# Adafruit_SMT_Datalogger_Shield_rev_C.net
KiCad netlist of a schematic drawn in EAGLE
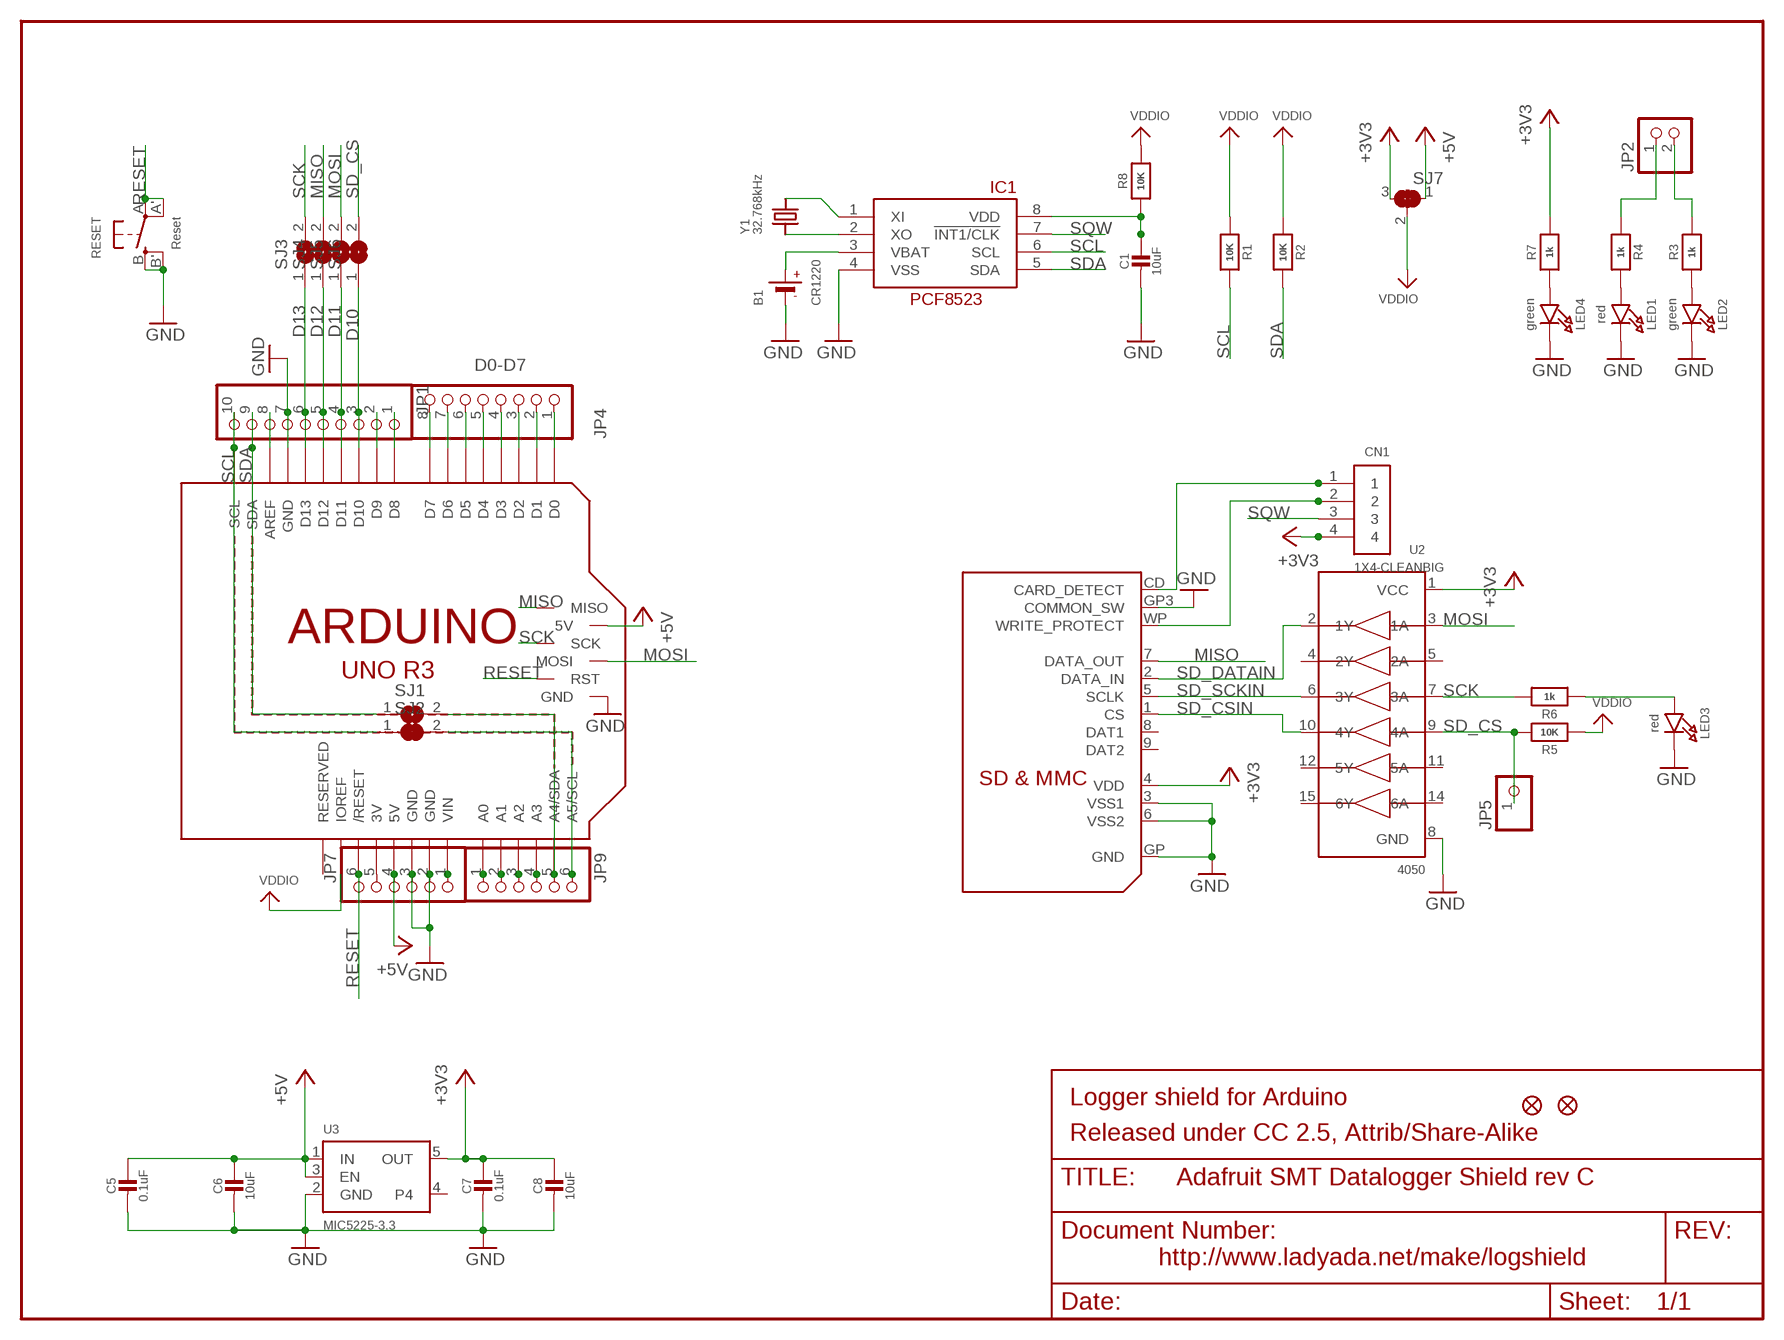
[diagram p0: schematic, sheet 1]

(export (version "E")
  (design (tool "Eeschema 10.0.6"))
  (components
    (comp (ref "B1")
      (value "CR1220")
      (footprint "eagle-import:CR1220")
      (libsource (lib "eagle-import") (part "BATTERYCR1220_SMT"))
    )
    (comp (ref "C1")
      (value "10uF")
      (footprint "eagle-import:0805-NO")
      (libsource (lib "eagle-import") (part "CAP_CERAMIC0805-NOOUTLINE"))
    )
    (comp (ref "C5")
      (value "0.1uF")
      (footprint "eagle-import:0805-NO")
      (libsource (lib "eagle-import") (part "CAP_CERAMIC0805-NOOUTLINE"))
    )
    (comp (ref "C6")
      (value "10uF")
      (footprint "eagle-import:0805-NO")
      (libsource (lib "eagle-import") (part "CAP_CERAMIC0805-NOOUTLINE"))
    )
    (comp (ref "C7")
      (value "0.1uF")
      (footprint "eagle-import:0805-NO")
      (libsource (lib "eagle-import") (part "CAP_CERAMIC0805-NOOUTLINE"))
    )
    (comp (ref "C8")
      (value "10uF")
      (footprint "eagle-import:0805-NO")
      (libsource (lib "eagle-import") (part "CAP_CERAMIC0805-NOOUTLINE"))
    )
    (comp (ref "CN1")
      (value "1X4-CLEANBIG")
      (footprint "eagle-import:1X04-CLEANBIG")
      (libsource (lib "eagle-import") (part "1X4-CLEANBIG"))
    )
    (comp (ref "FID1")
      (value "FIDUCIAL_1MM")
      (footprint "eagle-import:FIDUCIAL_1MM")
      (libsource (lib "eagle-import") (part "FIDUCIAL_1MM"))
    )
    (comp (ref "FID3")
      (value "FIDUCIAL_1MM")
      (footprint "eagle-import:FIDUCIAL_1MM")
      (libsource (lib "eagle-import") (part "FIDUCIAL_1MM"))
    )
    (comp (ref "IC1")
      (value "PCF8523T")
      (footprint "eagle-import:SOIC8_150MIL")
      (libsource (lib "eagle-import") (part "RTC_PCF8523T"))
    )
    (comp (ref "JP1")
      (value "HEADER-1X1070MIL")
      (footprint "eagle-import:1X10_ROUND70")
      (libsource (lib "eagle-import") (part "HEADER-1X1070MIL"))
    )
    (comp (ref "JP2")
      (value "HEADER-1X2ROUND")
      (footprint "eagle-import:1X02_ROUND")
      (libsource (lib "eagle-import") (part "HEADER-1X2ROUND"))
    )
    (comp (ref "JP4")
      (value "D0-D7")
      (footprint "eagle-import:1X08-BIG")
      (libsource (lib "eagle-import") (part "PINHD-1X8BIG"))
    )
    (comp (ref "JP5")
      (value "HEADER-1X1ROUND")
      (footprint "eagle-import:1X01_ROUND")
      (libsource (lib "eagle-import") (part "HEADER-1X1ROUND"))
    )
    (comp (ref "JP7")
      (value "PINHD-1X6B")
      (footprint "eagle-import:1X06-BIG")
      (libsource (lib "eagle-import") (part "PINHD-1X6B"))
    )
    (comp (ref "JP9")
      (value "PINHD-1X6B")
      (footprint "eagle-import:1X06-BIG")
      (libsource (lib "eagle-import") (part "PINHD-1X6B"))
    )
    (comp (ref "LED1")
      (value "red")
      (footprint "eagle-import:CHIPLED_0805_NOOUTLINE")
      (libsource (lib "eagle-import") (part "LED0805_NOOUTLINE"))
    )
    (comp (ref "LED2")
      (value "green")
      (footprint "eagle-import:CHIPLED_0805_NOOUTLINE")
      (libsource (lib "eagle-import") (part "LED0805_NOOUTLINE"))
    )
    (comp (ref "LED3")
      (value "red")
      (footprint "eagle-import:CHIPLED_0805_NOOUTLINE")
      (libsource (lib "eagle-import") (part "LED0805_NOOUTLINE"))
    )
    (comp (ref "LED4")
      (value "green")
      (footprint "eagle-import:CHIPLED_0805_NOOUTLINE")
      (libsource (lib "eagle-import") (part "LED0805_NOOUTLINE"))
    )
    (comp (ref "M1")
      (value "ARDUINO_R3_ICSP_NODIM")
      (footprint "eagle-import:ARDUINOR3_ICSP_NODIM")
      (libsource (lib "eagle-import") (part "ARDUINO_R3_ICSP_NODIM"))
    )
    (comp (ref "R1")
      (value "10K")
      (footprint "eagle-import:0805-NO")
      (libsource (lib "eagle-import") (part "RESISTOR0805_NOOUTLINE"))
    )
    (comp (ref "R2")
      (value "10K")
      (footprint "eagle-import:0805-NO")
      (libsource (lib "eagle-import") (part "RESISTOR0805_NOOUTLINE"))
    )
    (comp (ref "R3")
      (value "1k")
      (footprint "eagle-import:0805-NO")
      (libsource (lib "eagle-import") (part "RESISTOR0805_NOOUTLINE"))
    )
    (comp (ref "R4")
      (value "1k")
      (footprint "eagle-import:0805-NO")
      (libsource (lib "eagle-import") (part "RESISTOR0805_NOOUTLINE"))
    )
    (comp (ref "R5")
      (value "10K")
      (footprint "eagle-import:0805-NO")
      (libsource (lib "eagle-import") (part "RESISTOR0805_NOOUTLINE"))
    )
    (comp (ref "R6")
      (value "1k")
      (footprint "eagle-import:0805-NO")
      (libsource (lib "eagle-import") (part "RESISTOR0805_NOOUTLINE"))
    )
    (comp (ref "R7")
      (value "1k")
      (footprint "eagle-import:0805-NO")
      (libsource (lib "eagle-import") (part "RESISTOR0805_NOOUTLINE"))
    )
    (comp (ref "R8")
      (value "10K")
      (footprint "eagle-import:0805-NO")
      (libsource (lib "eagle-import") (part "RESISTOR0805_NOOUTLINE"))
    )
    (comp (ref "RESET")
      (value "Reset")
      (footprint "eagle-import:EVQ-Q2_SMALLER")
      (libsource (lib "eagle-import") (part "SWITCH_TACT_SMT_EVQQ2_SMALL"))
    )
    (comp (ref "SJ1")
      (value "SOLDERJUMPER")
      (footprint "eagle-import:SOLDERJUMPER_ARROW_NOPASTE")
      (libsource (lib "eagle-import") (part "SOLDERJUMPER"))
    )
    (comp (ref "SJ2")
      (value "SOLDERJUMPER")
      (footprint "eagle-import:SOLDERJUMPER_ARROW_NOPASTE")
      (libsource (lib "eagle-import") (part "SOLDERJUMPER"))
    )
    (comp (ref "SJ3")
      (value "SOLDERJUMPER")
      (footprint "eagle-import:SOLDERJUMPER_ARROW_NOPASTE")
      (libsource (lib "eagle-import") (part "SOLDERJUMPER"))
    )
    (comp (ref "SJ4")
      (value "SOLDERJUMPER")
      (footprint "eagle-import:SOLDERJUMPER_ARROW_NOPASTE")
      (libsource (lib "eagle-import") (part "SOLDERJUMPER"))
    )
    (comp (ref "SJ5")
      (value "SOLDERJUMPER")
      (footprint "eagle-import:SOLDERJUMPER_ARROW_NOPASTE")
      (libsource (lib "eagle-import") (part "SOLDERJUMPER"))
    )
    (comp (ref "SJ6")
      (value "SOLDERJUMPERCLOSED")
      (footprint "eagle-import:SOLDERJUMPER_CLOSEDWIRE")
      (libsource (lib "eagle-import") (part "SOLDERJUMPERCLOSED"))
    )
    (comp (ref "SJ7")
      (value "SOLDERJUMPER_2WAY")
      (footprint "eagle-import:SOLDERJUMPER_2WAY_OPEN_NOPASTE")
      (libsource (lib "eagle-import") (part "SOLDERJUMPER_2WAY"))
    )
    (comp (ref "U$2")
      (value "SDMMC06132")
      (footprint "eagle-import:06132")
      (libsource (lib "eagle-import") (part "SDMMC06132"))
    )
    (comp (ref "U2")
      (value "4050")
      (footprint "eagle-import:SOIC16")
      (libsource (lib "eagle-import") (part "74HC4050D"))
    )
    (comp (ref "U3")
      (value "MIC5225-3.3")
      (footprint "eagle-import:SOT23-5")
      (libsource (lib "eagle-import") (part "VREG_SOT23-5"))
    )
    (comp (ref "Y1")
      (value "32.768kHz")
      (footprint "eagle-import:CRYSTAL_8X3.8")
      (libsource (lib "eagle-import") (part "CRYSTAL8.0X3.8"))
    )
  )
  (nets
    (net (code "1") (name "+3V3") (class "Default")
      (node (ref "C7") (pin "1") (pinfunction "1_1") (pintype "passive"))
      (node (ref "C8") (pin "1") (pinfunction "1_1") (pintype "passive"))
      (node (ref "CN1") (pin "4") (pinfunction "4_4") (pintype "bidirectional"))
      (node (ref "R7") (pin "2") (pinfunction "2_2") (pintype "passive"))
      (node (ref "SJ7") (pin "3") (pinfunction "3_3") (pintype "passive"))
      (node (ref "U$2") (pin "4") (pinfunction "VDD_4") (pintype "power_in"))
      (node (ref "U2") (pin "1") (pinfunction "VCC_1") (pintype "bidirectional"))
      (node (ref "U3") (pin "5") (pinfunction "OUT_5") (pintype "power_in"))
    )
    (net (code "2") (name "+5V") (class "Default")
      (node (ref "C5") (pin "1") (pinfunction "1_1") (pintype "passive"))
      (node (ref "C6") (pin "1") (pinfunction "1_1") (pintype "passive"))
      (node (ref "JP7") (pin "4") (pinfunction "4_4") (pintype "passive"))
      (node (ref "M1") (pin "5V") (pinfunction "5V_5V") (pintype "power_in"))
      (node (ref "M1") (pin "5V_ICSP") (pinfunction "5V_5V_ICSP") (pintype "passive"))
      (node (ref "SJ7") (pin "1") (pinfunction "1_1") (pintype "passive"))
      (node (ref "U3") (pin "1") (pinfunction "IN_1") (pintype "power_in"))
      (node (ref "U3") (pin "3") (pinfunction "EN_3") (pintype "input"))
    )
    (net (code "3") (name "/D10") (class "Default")
      (node (ref "JP1") (pin "3") (pinfunction "3_3") (pintype "passive"))
      (node (ref "M1") (pin "D10") (pinfunction "D10_D10") (pintype "bidirectional"))
      (node (ref "SJ6") (pin "1") (pinfunction "1_1") (pintype "passive"))
    )
    (net (code "4") (name "/D11") (class "Default")
      (node (ref "JP1") (pin "4") (pinfunction "4_4") (pintype "passive"))
      (node (ref "M1") (pin "D11") (pinfunction "D11_D11") (pintype "bidirectional"))
      (node (ref "SJ5") (pin "1") (pinfunction "1_1") (pintype "passive"))
    )
    (net (code "5") (name "/D12") (class "Default")
      (node (ref "JP1") (pin "5") (pinfunction "5_5") (pintype "passive"))
      (node (ref "M1") (pin "D12") (pinfunction "D12_D12") (pintype "bidirectional"))
      (node (ref "SJ4") (pin "1") (pinfunction "1_1") (pintype "passive"))
    )
    (net (code "6") (name "/D13") (class "Default")
      (node (ref "JP1") (pin "6") (pinfunction "6_6") (pintype "passive"))
      (node (ref "M1") (pin "D13") (pinfunction "D13_D13") (pintype "bidirectional"))
      (node (ref "SJ3") (pin "1") (pinfunction "1_1") (pintype "passive"))
    )
    (net (code "7") (name "/MISO") (class "Default")
      (node (ref "M1") (pin "MISO") (pinfunction "MISO_MISO") (pintype "passive"))
      (node (ref "SJ4") (pin "2") (pinfunction "2_2") (pintype "passive"))
      (node (ref "U$2") (pin "7") (pinfunction "DATA_OUT_7") (pintype "output"))
    )
    (net (code "8") (name "/MOSI") (class "Default")
      (node (ref "M1") (pin "MOSI") (pinfunction "MOSI_MOSI") (pintype "passive"))
      (node (ref "SJ5") (pin "2") (pinfunction "2_2") (pintype "passive"))
      (node (ref "U2") (pin "3") (pinfunction "1A_3") (pintype "bidirectional"))
    )
    (net (code "9") (name "/RESET") (class "Default")
      (node (ref "JP7") (pin "6") (pinfunction "6_6") (pintype "passive"))
      (node (ref "M1") (pin "RESET") (pinfunction "/RESET_RESET") (pintype "bidirectional"))
      (node (ref "M1") (pin "RESET_ICSP") (pinfunction "RST_RESET_ICSP") (pintype "passive"))
      (node (ref "RESET") (pin "A") (pinfunction "P_A") (pintype "passive"))
      (node (ref "RESET") (pin "A'") (pinfunction "P1_A'") (pintype "passive"))
    )
    (net (code "10") (name "/SCK") (class "Default")
      (node (ref "M1") (pin "SCK") (pinfunction "SCK_SCK") (pintype "passive"))
      (node (ref "R6") (pin "2") (pinfunction "2_2") (pintype "passive"))
      (node (ref "SJ3") (pin "2") (pinfunction "2_2") (pintype "passive"))
      (node (ref "U2") (pin "7") (pinfunction "3A_7") (pintype "bidirectional"))
    )
    (net (code "11") (name "/SCL") (class "Default")
      (node (ref "IC1") (pin "6") (pinfunction "SCL_6") (pintype "bidirectional"))
      (node (ref "JP1") (pin "10") (pinfunction "10_10") (pintype "passive"))
      (node (ref "M1") (pin "SCL") (pinfunction "SCL_SCL") (pintype "bidirectional"))
      (node (ref "R1") (pin "2") (pinfunction "2_2") (pintype "passive"))
      (node (ref "SJ2") (pin "1") (pinfunction "1_1") (pintype "passive"))
    )
    (net (code "12") (name "/SDA") (class "Default")
      (node (ref "IC1") (pin "5") (pinfunction "SDA_5") (pintype "bidirectional"))
      (node (ref "JP1") (pin "9") (pinfunction "9_9") (pintype "passive"))
      (node (ref "M1") (pin "SDA") (pinfunction "SDA_SDA") (pintype "bidirectional"))
      (node (ref "R2") (pin "2") (pinfunction "2_2") (pintype "passive"))
      (node (ref "SJ1") (pin "1") (pinfunction "1_1") (pintype "passive"))
    )
    (net (code "13") (name "/SD_CS") (class "Default")
      (node (ref "JP5") (pin "1") (pinfunction "1_1") (pintype "passive"))
      (node (ref "R5") (pin "2") (pinfunction "2_2") (pintype "passive"))
      (node (ref "SJ6") (pin "2") (pinfunction "2_2") (pintype "passive"))
      (node (ref "U2") (pin "9") (pinfunction "4A_9") (pintype "bidirectional"))
    )
    (net (code "14") (name "/SD_CSIN") (class "Default")
      (node (ref "U$2") (pin "1") (pinfunction "CS_1") (pintype "input"))
      (node (ref "U2") (pin "10") (pinfunction "4Y_10") (pintype "bidirectional"))
    )
    (net (code "15") (name "/SD_DATAIN") (class "Default")
      (node (ref "U$2") (pin "2") (pinfunction "DATA_IN_2") (pintype "input"))
      (node (ref "U2") (pin "2") (pinfunction "1Y_2") (pintype "bidirectional"))
    )
    (net (code "16") (name "/SD_SCKIN") (class "Default")
      (node (ref "U$2") (pin "5") (pinfunction "SCLK_5") (pintype "input"))
      (node (ref "U2") (pin "6") (pinfunction "3Y_6") (pintype "bidirectional"))
    )
    (net (code "17") (name "/SQW") (class "Default")
      (node (ref "CN1") (pin "3") (pinfunction "3_3") (pintype "bidirectional"))
      (node (ref "IC1") (pin "7") (pinfunction "~{INT1/CLK}_7") (pintype "output"))
    )
    (net (code "18") (name "GND") (class "Default")
      (node (ref "B1") (pin "-") (pinfunction "-_-") (pintype "passive"))
      (node (ref "C1") (pin "2") (pinfunction "2_2") (pintype "passive"))
      (node (ref "C5") (pin "2") (pinfunction "2_2") (pintype "passive"))
      (node (ref "C6") (pin "2") (pinfunction "2_2") (pintype "passive"))
      (node (ref "C7") (pin "2") (pinfunction "2_2") (pintype "passive"))
      (node (ref "C8") (pin "2") (pinfunction "2_2") (pintype "passive"))
      (node (ref "IC1") (pin "4") (pinfunction "VSS_4") (pintype "power_in"))
      (node (ref "JP1") (pin "7") (pinfunction "7_7") (pintype "passive"))
      (node (ref "JP7") (pin "2") (pinfunction "2_2") (pintype "passive"))
      (node (ref "JP7") (pin "3") (pinfunction "3_3") (pintype "passive"))
      (node (ref "LED1") (pin "C") (pinfunction "C_C") (pintype "passive"))
      (node (ref "LED2") (pin "C") (pinfunction "C_C") (pintype "passive"))
      (node (ref "LED3") (pin "C") (pinfunction "C_C") (pintype "passive"))
      (node (ref "LED4") (pin "C") (pinfunction "C_C") (pintype "passive"))
      (node (ref "M1") (pin "GND") (pinfunction "GND_GND") (pintype "power_in"))
      (node (ref "M1") (pin "GND@1") (pinfunction "GND_GND@1") (pintype "power_in"))
      (node (ref "M1") (pin "GND@2") (pinfunction "GND_GND@2") (pintype "passive"))
      (node (ref "M1") (pin "GND@3") (pinfunction "GND_GND@3") (pintype "power_in"))
      (node (ref "RESET") (pin "B") (pinfunction "S_B") (pintype "passive"))
      (node (ref "RESET") (pin "B'") (pinfunction "S1_B'") (pintype "passive"))
      (node (ref "U$2") (pin "3") (pinfunction "VSS1_3") (pintype "power_in"))
      (node (ref "U$2") (pin "6") (pinfunction "VSS2_6") (pintype "power_in"))
      (node (ref "U$2") (pin "GP") (pinfunction "GND_GP") (pintype "power_in"))
      (node (ref "U$2") (pin "GP3") (pinfunction "COMMON_SW_GP3") (pintype "passive"))
      (node (ref "U2") (pin "8") (pinfunction "GND_8") (pintype "bidirectional"))
      (node (ref "U3") (pin "2") (pinfunction "GND_2") (pintype "power_in"))
    )
    (net (code "19") (name "Net-(IC1-VBAT)") (class "Default")
      (node (ref "B1") (pin "+$1") (pinfunction "+_+$1") (pintype "passive"))
      (node (ref "B1") (pin "+$2") (pinfunction "+_+$2") (pintype "passive"))
      (node (ref "IC1") (pin "3") (pinfunction "VBAT_3") (pintype "power_in"))
    )
    (net (code "20") (name "Net-(IC1-VDD)") (class "Default")
      (node (ref "C1") (pin "1") (pinfunction "1_1") (pintype "passive"))
      (node (ref "IC1") (pin "8") (pinfunction "VDD_8") (pintype "power_in"))
      (node (ref "R8") (pin "1") (pinfunction "1_1") (pintype "passive"))
    )
    (net (code "21") (name "Net-(IC1-XI)") (class "Default")
      (node (ref "IC1") (pin "1") (pinfunction "XI_1") (pintype "input"))
      (node (ref "Y1") (pin "P$4") (pinfunction "2_P$4") (pintype "passive"))
    )
    (net (code "22") (name "Net-(IC1-XO)") (class "Default")
      (node (ref "IC1") (pin "2") (pinfunction "XO_2") (pintype "output"))
      (node (ref "Y1") (pin "P$1") (pinfunction "1_P$1") (pintype "passive"))
    )
    (net (code "23") (name "Net-(JP1-Pad1)") (class "Default")
      (node (ref "JP1") (pin "1") (pinfunction "1_1") (pintype "passive"))
      (node (ref "M1") (pin "D8") (pinfunction "D8_D8") (pintype "bidirectional"))
    )
    (net (code "24") (name "Net-(JP1-Pad2)") (class "Default")
      (node (ref "JP1") (pin "2") (pinfunction "2_2") (pintype "passive"))
      (node (ref "M1") (pin "D9") (pinfunction "D9_D9") (pintype "bidirectional"))
    )
    (net (code "25") (name "Net-(JP1-Pad8)") (class "Default")
      (node (ref "JP1") (pin "8") (pinfunction "8_8") (pintype "passive"))
      (node (ref "M1") (pin "AREF") (pinfunction "AREF_AREF") (pintype "bidirectional"))
    )
    (net (code "26") (name "Net-(JP2-Pad1)") (class "Default")
      (node (ref "JP2") (pin "1") (pinfunction "1_1") (pintype "passive"))
      (node (ref "R4") (pin "1") (pinfunction "1_1") (pintype "passive"))
    )
    (net (code "27") (name "Net-(JP2-Pad2)") (class "Default")
      (node (ref "JP2") (pin "2") (pinfunction "2_2") (pintype "passive"))
      (node (ref "R3") (pin "2") (pinfunction "2_2") (pintype "passive"))
    )
    (net (code "28") (name "Net-(JP4-Pad1)") (class "Default")
      (node (ref "JP4") (pin "1") (pinfunction "1_1") (pintype "passive"))
      (node (ref "M1") (pin "D0") (pinfunction "D0_D0") (pintype "bidirectional"))
    )
    (net (code "29") (name "Net-(JP4-Pad2)") (class "Default")
      (node (ref "JP4") (pin "2") (pinfunction "2_2") (pintype "passive"))
      (node (ref "M1") (pin "D1") (pinfunction "D1_D1") (pintype "bidirectional"))
    )
    (net (code "30") (name "Net-(JP4-Pad3)") (class "Default")
      (node (ref "JP4") (pin "3") (pinfunction "3_3") (pintype "passive"))
      (node (ref "M1") (pin "D2") (pinfunction "D2_D2") (pintype "bidirectional"))
    )
    (net (code "31") (name "Net-(JP4-Pad4)") (class "Default")
      (node (ref "JP4") (pin "4") (pinfunction "4_4") (pintype "passive"))
      (node (ref "M1") (pin "D3") (pinfunction "D3_D3") (pintype "bidirectional"))
    )
    (net (code "32") (name "Net-(JP4-Pad5)") (class "Default")
      (node (ref "JP4") (pin "5") (pinfunction "5_5") (pintype "passive"))
      (node (ref "M1") (pin "D4") (pinfunction "D4_D4") (pintype "bidirectional"))
    )
    (net (code "33") (name "Net-(JP4-Pad6)") (class "Default")
      (node (ref "JP4") (pin "6") (pinfunction "6_6") (pintype "passive"))
      (node (ref "M1") (pin "D5") (pinfunction "D5_D5") (pintype "bidirectional"))
    )
    (net (code "34") (name "Net-(JP4-Pad7)") (class "Default")
      (node (ref "JP4") (pin "7") (pinfunction "7_7") (pintype "passive"))
      (node (ref "M1") (pin "D6") (pinfunction "D6_D6") (pintype "bidirectional"))
    )
    (net (code "35") (name "Net-(JP4-Pad8)") (class "Default")
      (node (ref "JP4") (pin "8") (pinfunction "8_8") (pintype "passive"))
      (node (ref "M1") (pin "D7") (pinfunction "D7_D7") (pintype "bidirectional"))
    )
    (net (code "36") (name "Net-(JP7-Pad1)") (class "Default")
      (node (ref "JP7") (pin "1") (pinfunction "1_1") (pintype "passive"))
      (node (ref "M1") (pin "VIN") (pinfunction "VIN_VIN") (pintype "power_in"))
    )
    (net (code "37") (name "Net-(JP7-Pad5)") (class "Default")
      (node (ref "JP7") (pin "5") (pinfunction "5_5") (pintype "passive"))
      (node (ref "M1") (pin "3V") (pinfunction "3V_3V") (pintype "power_in"))
    )
    (net (code "38") (name "Net-(JP9-Pad1)") (class "Default")
      (node (ref "JP9") (pin "1") (pinfunction "1_1") (pintype "passive"))
      (node (ref "M1") (pin "A0") (pinfunction "A0_A0") (pintype "bidirectional"))
    )
    (net (code "39") (name "Net-(JP9-Pad2)") (class "Default")
      (node (ref "JP9") (pin "2") (pinfunction "2_2") (pintype "passive"))
      (node (ref "M1") (pin "A1") (pinfunction "A1_A1") (pintype "bidirectional"))
    )
    (net (code "40") (name "Net-(JP9-Pad3)") (class "Default")
      (node (ref "JP9") (pin "3") (pinfunction "3_3") (pintype "passive"))
      (node (ref "M1") (pin "A2") (pinfunction "A2_A2") (pintype "bidirectional"))
    )
    (net (code "41") (name "Net-(JP9-Pad4)") (class "Default")
      (node (ref "JP9") (pin "4") (pinfunction "4_4") (pintype "passive"))
      (node (ref "M1") (pin "A3") (pinfunction "A3_A3") (pintype "bidirectional"))
    )
    (net (code "42") (name "Net-(LED1-PadA)") (class "Default")
      (node (ref "LED1") (pin "A") (pinfunction "A_A") (pintype "passive"))
      (node (ref "R4") (pin "2") (pinfunction "2_2") (pintype "passive"))
    )
    (net (code "43") (name "Net-(LED2-PadA)") (class "Default")
      (node (ref "LED2") (pin "A") (pinfunction "A_A") (pintype "passive"))
      (node (ref "R3") (pin "1") (pinfunction "1_1") (pintype "passive"))
    )
    (net (code "44") (name "Net-(LED3-PadA)") (class "Default")
      (node (ref "LED3") (pin "A") (pinfunction "A_A") (pintype "passive"))
      (node (ref "R6") (pin "1") (pinfunction "1_1") (pintype "passive"))
    )
    (net (code "45") (name "Net-(LED4-PadA)") (class "Default")
      (node (ref "LED4") (pin "A") (pinfunction "A_A") (pintype "passive"))
      (node (ref "R7") (pin "1") (pinfunction "1_1") (pintype "passive"))
    )
    (net (code "46") (name "Net-(M1-A4{slash}SDA)") (class "Default")
      (node (ref "JP9") (pin "5") (pinfunction "5_5") (pintype "passive"))
      (node (ref "M1") (pin "A4") (pinfunction "A4/SDA_A4") (pintype "bidirectional"))
      (node (ref "SJ1") (pin "2") (pinfunction "2_2") (pintype "passive"))
    )
    (net (code "47") (name "Net-(M1-A5{slash}SCL)") (class "Default")
      (node (ref "JP9") (pin "6") (pinfunction "6_6") (pintype "passive"))
      (node (ref "M1") (pin "A5") (pinfunction "A5/SCL_A5") (pintype "bidirectional"))
      (node (ref "SJ2") (pin "2") (pinfunction "2_2") (pintype "passive"))
    )
    (net (code "48") (name "Net-(U$2-CARD_DETECT)") (class "Default")
      (node (ref "CN1") (pin "1") (pinfunction "1_1") (pintype "bidirectional"))
      (node (ref "U$2") (pin "CD") (pinfunction "CARD_DETECT_CD") (pintype "passive"))
    )
    (net (code "49") (name "Net-(U$2-WRITE_PROTECT)") (class "Default")
      (node (ref "CN1") (pin "2") (pinfunction "2_2") (pintype "bidirectional"))
      (node (ref "U$2") (pin "WP") (pinfunction "WRITE_PROTECT_WP") (pintype "passive"))
    )
    (net (code "50") (name "VDDIO") (class "Default")
      (node (ref "M1") (pin "IOREF") (pinfunction "IOREF_IOREF") (pintype "output"))
      (node (ref "R1") (pin "1") (pinfunction "1_1") (pintype "passive"))
      (node (ref "R2") (pin "1") (pinfunction "1_1") (pintype "passive"))
      (node (ref "R5") (pin "1") (pinfunction "1_1") (pintype "passive"))
      (node (ref "R8") (pin "2") (pinfunction "2_2") (pintype "passive"))
      (node (ref "SJ7") (pin "2") (pinfunction "2_2") (pintype "passive"))
    )
    (net (code "51") (name "unconnected-(M1-PadRESERVED)") (class "Default")
      (node (ref "M1") (pin "RESERVED") (pinfunction "RESERVED_RESERVED") (pintype "no_connect"))
    )
    (net (code "52") (name "unconnected-(U$2-DAT1-Pad8)") (class "Default")
      (node (ref "U$2") (pin "8") (pinfunction "DAT1_8") (pintype "bidirectional"))
    )
    (net (code "53") (name "unconnected-(U$2-DAT2-Pad9)") (class "Default")
      (node (ref "U$2") (pin "9") (pinfunction "DAT2_9") (pintype "bidirectional"))
    )
    (net (code "54") (name "unconnected-(U2-2A-Pad5)") (class "Default")
      (node (ref "U2") (pin "5") (pinfunction "2A_5") (pintype "bidirectional"))
    )
    (net (code "55") (name "unconnected-(U2-2Y-Pad4)") (class "Default")
      (node (ref "U2") (pin "4") (pinfunction "2Y_4") (pintype "bidirectional"))
    )
    (net (code "56") (name "unconnected-(U2-5A-Pad11)") (class "Default")
      (node (ref "U2") (pin "11") (pinfunction "5A_11") (pintype "bidirectional"))
    )
    (net (code "57") (name "unconnected-(U2-5Y-Pad12)") (class "Default")
      (node (ref "U2") (pin "12") (pinfunction "5Y_12") (pintype "bidirectional"))
    )
    (net (code "58") (name "unconnected-(U2-6A-Pad14)") (class "Default")
      (node (ref "U2") (pin "14") (pinfunction "6A_14") (pintype "bidirectional"))
    )
    (net (code "59") (name "unconnected-(U2-6Y-Pad15)") (class "Default")
      (node (ref "U2") (pin "15") (pinfunction "6Y_15") (pintype "bidirectional"))
    )
    (net (code "60") (name "unconnected-(U3-P4-Pad4)") (class "Default")
      (node (ref "U3") (pin "4") (pinfunction "P4_4") (pintype "bidirectional"))
    )
  )
)
